# MotorControl.net
KiCad netlist of a schematic drawn in Altium Designer
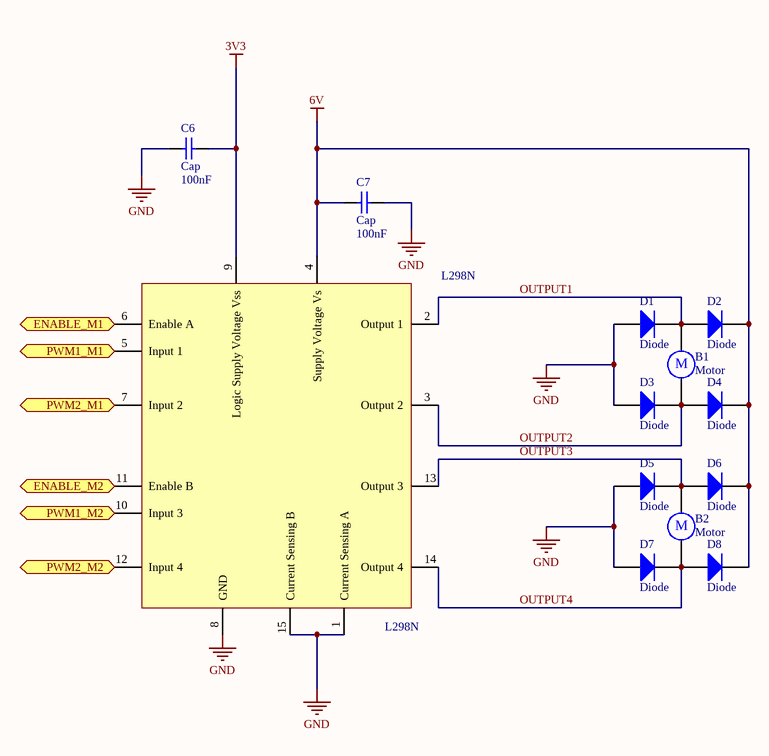
[diagram p0: MotorControl.SchDoc]

(export (version "E")
  (design (tool "Eeschema 10.0.6"))
  (components
    (comp (ref "B1")
      (value "Motor")
      (footprint "BORNIER")
      (description "Motor, General Kind")
      (fields (field (name "PUBLISHER") "Altium Limited"))
      (libsource (lib "Miscellaneous Devices") (part "Motor"))
    )
    (comp (ref "B2")
      (value "Motor")
      (footprint "BORNIER")
      (description "Motor, General Kind")
      (fields (field (name "PUBLISHER") "Altium Limited"))
      (libsource (lib "Miscellaneous Devices") (part "Motor"))
    )
    (comp (ref "C6")
      (value "Cap")
      (footprint "CAPC1608N")
      (description "Capacitor")
      (fields (field (name "ALTIUM_VALUE") "100nF") (field (name "PUBLISHER") "Altium Limited"))
      (libsource (lib "Miscellaneous Devices") (part "Cap"))
    )
    (comp (ref "C7")
      (value "Cap")
      (footprint "CAPC1608N")
      (description "Capacitor")
      (fields (field (name "ALTIUM_VALUE") "100nF") (field (name "PUBLISHER") "Altium Limited"))
      (libsource (lib "Miscellaneous Devices") (part "Cap"))
    )
    (comp (ref "D1")
      (value "Diode")
      (footprint "DIODE")
      (description "Default Diode")
      (fields (field (name "PUBLISHER") "Altium Limited"))
      (libsource (lib "Miscellaneous Devices") (part "Diode"))
    )
    (comp (ref "D2")
      (value "Diode")
      (footprint "DIODE")
      (description "Default Diode")
      (fields (field (name "PUBLISHER") "Altium Limited"))
      (libsource (lib "Miscellaneous Devices") (part "Diode"))
    )
    (comp (ref "D3")
      (value "Diode")
      (footprint "DIODE")
      (description "Default Diode")
      (fields (field (name "PUBLISHER") "Altium Limited"))
      (libsource (lib "Miscellaneous Devices") (part "Diode"))
    )
    (comp (ref "D4")
      (value "Diode")
      (footprint "DIODE")
      (description "Default Diode")
      (fields (field (name "PUBLISHER") "Altium Limited"))
      (libsource (lib "Miscellaneous Devices") (part "Diode"))
    )
    (comp (ref "D5")
      (value "Diode")
      (footprint "DIODE")
      (description "Default Diode")
      (fields (field (name "PUBLISHER") "Altium Limited"))
      (libsource (lib "Miscellaneous Devices") (part "Diode"))
    )
    (comp (ref "D6")
      (value "Diode")
      (footprint "DIODE")
      (description "Default Diode")
      (fields (field (name "PUBLISHER") "Altium Limited"))
      (libsource (lib "Miscellaneous Devices") (part "Diode"))
    )
    (comp (ref "D7")
      (value "Diode")
      (footprint "DIODE")
      (description "Default Diode")
      (fields (field (name "PUBLISHER") "Altium Limited"))
      (libsource (lib "Miscellaneous Devices") (part "Diode"))
    )
    (comp (ref "D8")
      (value "Diode")
      (footprint "DIODE")
      (description "Default Diode")
      (fields (field (name "PUBLISHER") "Altium Limited"))
      (libsource (lib "Miscellaneous Devices") (part "Diode"))
    )
    (comp (ref "L298N") (value "L298N") (footprint "L298N") (libsource (lib "SCHLIB_Autobot") (part "L298N")))
  )
  (nets
    (net (code "1") (name "/ENABLE_M1") (class "Default")
      (node (ref "L298N") (pin "6") (pinfunction "Enable_A_6") (pintype "passive"))
    )
    (net (code "2") (name "/ENABLE_M2") (class "Default")
      (node (ref "L298N") (pin "11") (pinfunction "Enable_B_11") (pintype "passive"))
    )
    (net (code "3") (name "/OUTPUT1") (class "Default")
      (node (ref "B1") (pin "1") (pinfunction "1_1") (pintype "passive"))
      (node (ref "D1") (pin "2") (pinfunction "K_2") (pintype "passive"))
      (node (ref "D2") (pin "1") (pinfunction "A_1") (pintype "passive"))
      (node (ref "L298N") (pin "2") (pinfunction "Output_1_2") (pintype "passive"))
    )
    (net (code "4") (name "/OUTPUT2") (class "Default")
      (node (ref "B1") (pin "2") (pinfunction "2_2") (pintype "passive"))
      (node (ref "D3") (pin "2") (pinfunction "K_2") (pintype "passive"))
      (node (ref "D4") (pin "1") (pinfunction "A_1") (pintype "passive"))
      (node (ref "L298N") (pin "3") (pinfunction "Output_2_3") (pintype "passive"))
    )
    (net (code "5") (name "/OUTPUT3") (class "Default")
      (node (ref "B2") (pin "1") (pinfunction "1_1") (pintype "passive"))
      (node (ref "D5") (pin "2") (pinfunction "K_2") (pintype "passive"))
      (node (ref "D6") (pin "1") (pinfunction "A_1") (pintype "passive"))
      (node (ref "L298N") (pin "13") (pinfunction "Output_3_13") (pintype "passive"))
    )
    (net (code "6") (name "/OUTPUT4") (class "Default")
      (node (ref "B2") (pin "2") (pinfunction "2_2") (pintype "passive"))
      (node (ref "D7") (pin "2") (pinfunction "K_2") (pintype "passive"))
      (node (ref "D8") (pin "1") (pinfunction "A_1") (pintype "passive"))
      (node (ref "L298N") (pin "14") (pinfunction "Output_4_14") (pintype "passive"))
    )
    (net (code "7") (name "/PWM1_M1") (class "Default")
      (node (ref "L298N") (pin "5") (pinfunction "Input_1_5") (pintype "passive"))
    )
    (net (code "8") (name "/PWM1_M2") (class "Default")
      (node (ref "L298N") (pin "10") (pinfunction "Input_3_10") (pintype "passive"))
    )
    (net (code "9") (name "/PWM2_M1") (class "Default")
      (node (ref "L298N") (pin "7") (pinfunction "Input_2_7") (pintype "passive"))
    )
    (net (code "10") (name "/PWM2_M2") (class "Default")
      (node (ref "L298N") (pin "12") (pinfunction "Input_4_12") (pintype "passive"))
    )
    (net (code "11") (name "3V3") (class "Default")
      (node (ref "C6") (pin "1") (pinfunction "1_1") (pintype "passive"))
      (node (ref "L298N") (pin "9") (pinfunction "Logic_Supply_Voltage_Vss_9") (pintype "passive"))
    )
    (net (code "12") (name "6V") (class "Default")
      (node (ref "C7") (pin "1") (pinfunction "1_1") (pintype "passive"))
      (node (ref "D2") (pin "2") (pinfunction "K_2") (pintype "passive"))
      (node (ref "D4") (pin "2") (pinfunction "K_2") (pintype "passive"))
      (node (ref "D6") (pin "2") (pinfunction "K_2") (pintype "passive"))
      (node (ref "D8") (pin "2") (pinfunction "K_2") (pintype "passive"))
      (node (ref "L298N") (pin "4") (pinfunction "Supply_Voltage_Vs_4") (pintype "passive"))
    )
    (net (code "13") (name "GND") (class "Default")
      (node (ref "C6") (pin "2") (pinfunction "2_2") (pintype "passive"))
      (node (ref "C7") (pin "2") (pinfunction "2_2") (pintype "passive"))
      (node (ref "D1") (pin "1") (pinfunction "A_1") (pintype "passive"))
      (node (ref "D3") (pin "1") (pinfunction "A_1") (pintype "passive"))
      (node (ref "D5") (pin "1") (pinfunction "A_1") (pintype "passive"))
      (node (ref "D7") (pin "1") (pinfunction "A_1") (pintype "passive"))
      (node (ref "L298N") (pin "1") (pinfunction "Current_Sensing_A_1") (pintype "passive"))
      (node (ref "L298N") (pin "15") (pinfunction "Current_Sensing_B_15") (pintype "passive"))
      (node (ref "L298N") (pin "8") (pinfunction "GND_8") (pintype "passive"))
    )
  )
)
